# untitled.net
KiCad netlist of a schematic drawn in EAGLE
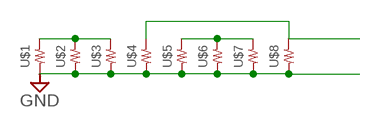
[diagram p0: schematic, sheet 1]

(export (version "E")
  (design (tool "Eeschema 10.0.6"))
  (components
    (comp (ref "U$1")
      (value "RESISTOR__SMD")
      (footprint "eagle-import:1608")
      (libsource (lib "eagle-import") (part "RESISTOR__SMD"))
    )
    (comp (ref "U$2")
      (value "RESISTOR__SMD")
      (footprint "eagle-import:1608")
      (libsource (lib "eagle-import") (part "RESISTOR__SMD"))
    )
    (comp (ref "U$3")
      (value "RESISTOR__SMD")
      (footprint "eagle-import:1608")
      (libsource (lib "eagle-import") (part "RESISTOR__SMD"))
    )
    (comp (ref "U$4")
      (value "RESISTOR__SMD")
      (footprint "eagle-import:1608")
      (libsource (lib "eagle-import") (part "RESISTOR__SMD"))
    )
    (comp (ref "U$5")
      (value "RESISTOR__SMD")
      (footprint "eagle-import:1608")
      (libsource (lib "eagle-import") (part "RESISTOR__SMD"))
    )
    (comp (ref "U$6")
      (value "RESISTOR__SMD")
      (footprint "eagle-import:1608")
      (libsource (lib "eagle-import") (part "RESISTOR__SMD"))
    )
    (comp (ref "U$7")
      (value "RESISTOR__SMD")
      (footprint "eagle-import:1608")
      (libsource (lib "eagle-import") (part "RESISTOR__SMD"))
    )
    (comp (ref "U$8")
      (value "RESISTOR__SMD")
      (footprint "eagle-import:1608")
      (libsource (lib "eagle-import") (part "RESISTOR__SMD"))
    )
  )
  (nets
    (net (code "1") (name "GND") (class "Default")
      (node (ref "U$1") (pin "1") (pinfunction "P$1_1") (pintype "passive"))
      (node (ref "U$2") (pin "1") (pinfunction "P$1_1") (pintype "passive"))
      (node (ref "U$3") (pin "1") (pinfunction "P$1_1") (pintype "passive"))
      (node (ref "U$4") (pin "1") (pinfunction "P$1_1") (pintype "passive"))
      (node (ref "U$5") (pin "1") (pinfunction "P$1_1") (pintype "passive"))
      (node (ref "U$6") (pin "1") (pinfunction "P$1_1") (pintype "passive"))
      (node (ref "U$7") (pin "1") (pinfunction "P$1_1") (pintype "passive"))
      (node (ref "U$8") (pin "1") (pinfunction "P$1_1") (pintype "passive"))
    )
    (net (code "2") (name "Net-(U$1-P$2)") (class "Default")
      (node (ref "U$1") (pin "2") (pinfunction "P$2_2") (pintype "passive"))
      (node (ref "U$2") (pin "2") (pinfunction "P$2_2") (pintype "passive"))
      (node (ref "U$3") (pin "2") (pinfunction "P$2_2") (pintype "passive"))
    )
    (net (code "3") (name "Net-(U$4-P$2)") (class "Default")
      (node (ref "U$4") (pin "2") (pinfunction "P$2_2") (pintype "passive"))
      (node (ref "U$8") (pin "2") (pinfunction "P$2_2") (pintype "passive"))
    )
    (net (code "4") (name "Net-(U$5-P$2)") (class "Default")
      (node (ref "U$5") (pin "2") (pinfunction "P$2_2") (pintype "passive"))
      (node (ref "U$6") (pin "2") (pinfunction "P$2_2") (pintype "passive"))
      (node (ref "U$7") (pin "2") (pinfunction "P$2_2") (pintype "passive"))
    )
  )
)
